# drivers.net
KiCad netlist of a schematic drawn in Altium Designer
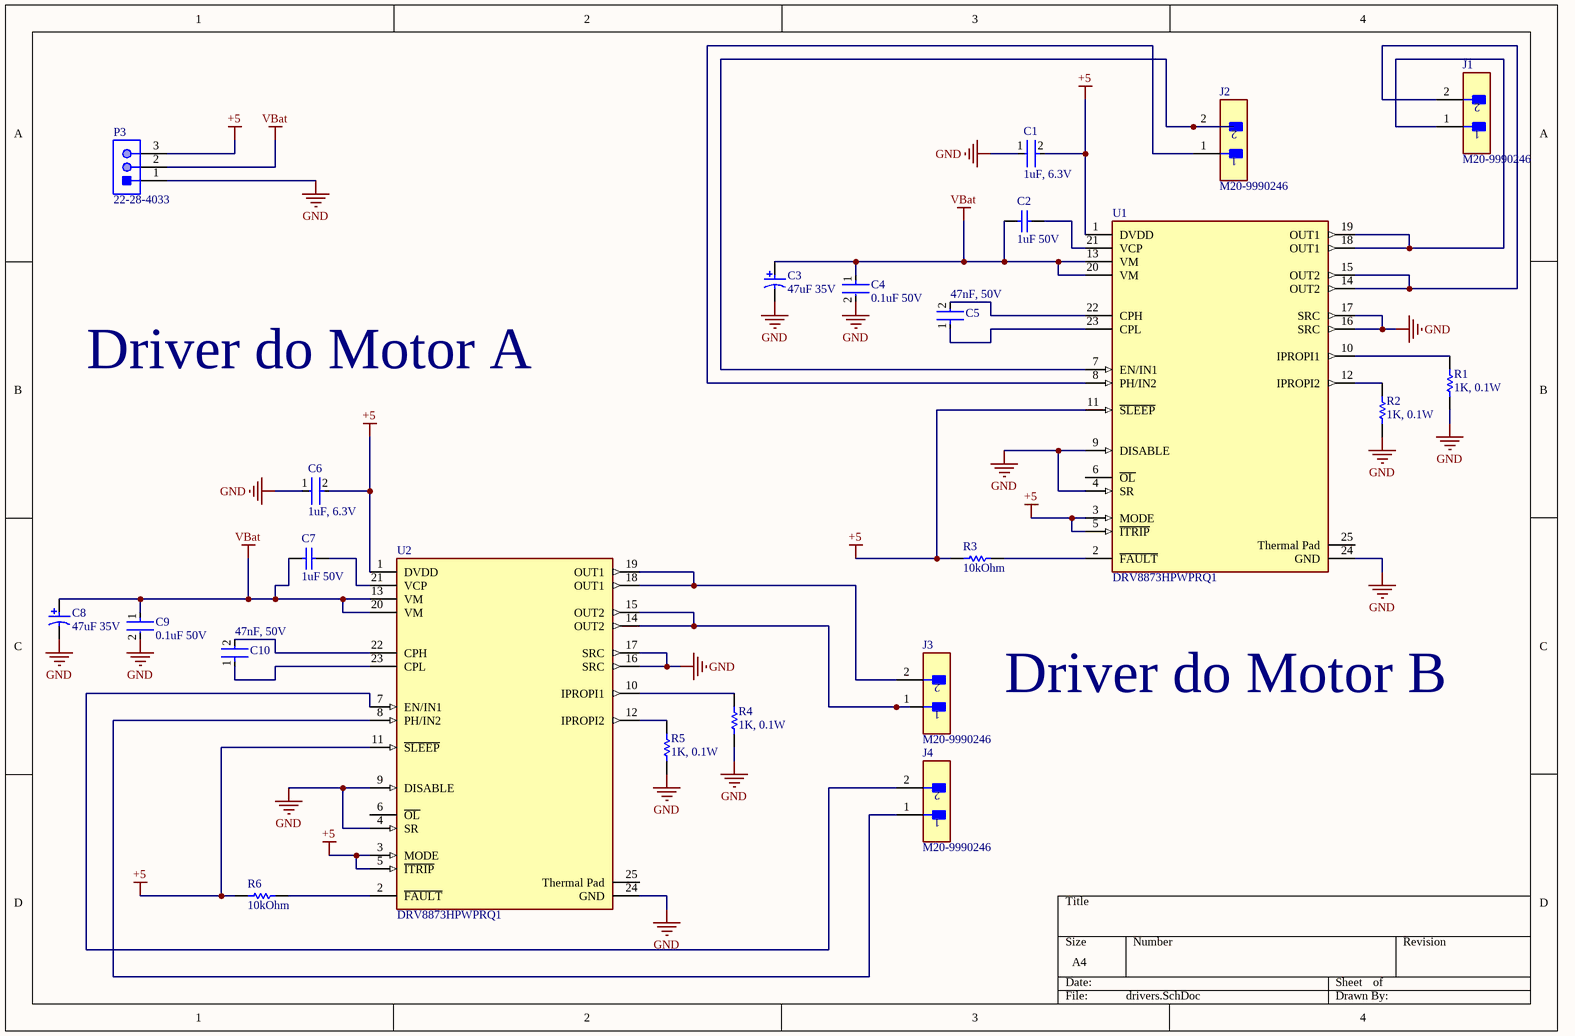
[diagram p0: drivers.SchDoc]

(export (version "E")
  (design (tool "Eeschema 10.0.6"))
  (components
    (comp (ref "C1")
      (value "1uF, 6.3V")
      (footprint "FP-GRM188-0_1-MFG")
      (description "CAP CER 1UF 6.3V X5R 0603")
      (fields (field (name "TOLERANCE") "10%") (field (name "VOLTAGE") "6.3V"))
      (libsource (lib "Altium Content Vault") (part "236180d848d6139a670b325ea6854c9"))
    )
    (comp (ref "C2")
      (value "1uF 50V")
      (footprint "CAPC1608X90X35ML10T25")
      (description "Chip Capacitor, 1 uF, +/- 10%, 50 V, -55 to 85 degC, 0603 (1608 Metric), RoHS, Tape and Reel")
      (fields (field (name "TOLERANCE") "±10%") (field (name "MANUFACTURER") "Taiyo Yuden"))
      (libsource (lib "Altium Content Vault") (part "CAP-NP-2"))
    )
    (comp (ref "C3")
      (value "47uF 35V")
      (footprint "PNSC-FP-V-D_V")
      (fields (field (name "MANUFACTURER") "Panasonic"))
      (libsource (lib "Altium Content Vault") (part "CAP-P-2"))
    )
    (comp (ref "C4")
      (value "0.1uF 50V")
      (footprint "FP-C0603-CJ-MFG")
      (description "CAP CER 0.1UF 50V X7R 0603")
      (fields (field (name "MANUFACTURER PART NUMBER") "C0603X104K5RACTU") (field (name "VOLTAGE") "50V"))
      (libsource (lib "Altium Content Vault") (part "11868f565c42a9108669ba33697ecf6"))
    )
    (comp (ref "C5")
      (value "47nF, 50V")
      (footprint "FP-C0603C-CF-MFG")
      (description "CAP CER 0.047UF 50V 10% X7R 0603")
      (fields (field (name "TOLERANCE") "0.1") (field (name "MANUFACTURER") "KEMET"))
      (libsource (lib "Altium Content Vault") (part "b4654b650e69147ec39a6b967a45e02"))
    )
    (comp (ref "C6")
      (value "1uF, 6.3V")
      (footprint "FP-GRM188-0_1-MFG")
      (description "CAP CER 1UF 6.3V X5R 0603")
      (fields (field (name "TOLERANCE") "10%") (field (name "VOLTAGE") "6.3V"))
      (libsource (lib "Altium Content Vault") (part "236180d848d6139a670b325ea6854c9"))
    )
    (comp (ref "C7")
      (value "1uF 50V")
      (footprint "CAPC1608X90X35ML10T25")
      (description "Chip Capacitor, 1 uF, +/- 10%, 50 V, -55 to 85 degC, 0603 (1608 Metric), RoHS, Tape and Reel")
      (fields (field (name "TOLERANCE") "±10%") (field (name "MANUFACTURER") "Taiyo Yuden"))
      (libsource (lib "Altium Content Vault") (part "CAP-NP-2"))
    )
    (comp (ref "C8")
      (value "47uF 35V")
      (footprint "PNSC-FP-V-D_V")
      (fields (field (name "MANUFACTURER") "Panasonic"))
      (libsource (lib "Altium Content Vault") (part "CAP-P-2"))
    )
    (comp (ref "C9")
      (value "0.1uF 50V")
      (footprint "FP-C0603-CJ-MFG")
      (description "CAP CER 0.1UF 50V X7R 0603")
      (fields (field (name "MANUFACTURER PART NUMBER") "C0603X104K5RACTU") (field (name "VOLTAGE") "50V"))
      (libsource (lib "Altium Content Vault") (part "11868f565c42a9108669ba33697ecf6"))
    )
    (comp (ref "C10")
      (value "47nF, 50V")
      (footprint "FP-C0603C-CF-MFG")
      (description "CAP CER 0.047UF 50V 10% X7R 0603")
      (fields (field (name "TOLERANCE") "0.1") (field (name "MANUFACTURER") "KEMET"))
      (libsource (lib "Altium Content Vault") (part "b4654b650e69147ec39a6b967a45e02"))
    )
    (comp (ref "J1")
      (value "M20-9990246")
      (footprint "FP-M20-9990246-MFG")
      (description "CONN HEADER VERT 2POS 2.54MM")
      (fields
        (field (name "OCTOPART") "https://octopart.com/m20-9990246-harwin-2590635")
        (field (name "MANUFACTURER") "Harwin")
      )
      (libsource (lib "Altium Content Vault") (part "3bc925449376181038e59eaffc5286c"))
    )
    (comp (ref "J2")
      (value "M20-9990246")
      (footprint "FP-M20-9990246-MFG")
      (description "CONN HEADER VERT 2POS 2.54MM")
      (fields
        (field (name "OCTOPART") "https://octopart.com/m20-9990246-harwin-2590635")
        (field (name "MANUFACTURER") "Harwin")
      )
      (libsource (lib "Altium Content Vault") (part "3bc925449376181038e59eaffc5286c"))
    )
    (comp (ref "J3")
      (value "M20-9990246")
      (footprint "FP-M20-9990246-MFG")
      (description "CONN HEADER VERT 2POS 2.54MM")
      (fields
        (field (name "OCTOPART") "https://octopart.com/m20-9990246-harwin-2590635")
        (field (name "MANUFACTURER") "Harwin")
      )
      (libsource (lib "Altium Content Vault") (part "3bc925449376181038e59eaffc5286c"))
    )
    (comp (ref "J4")
      (value "M20-9990246")
      (footprint "FP-M20-9990246-MFG")
      (description "CONN HEADER VERT 2POS 2.54MM")
      (fields
        (field (name "OCTOPART") "https://octopart.com/m20-9990246-harwin-2590635")
        (field (name "MANUFACTURER") "Harwin")
      )
      (libsource (lib "Altium Content Vault") (part "3bc925449376181038e59eaffc5286c"))
    )
    (comp (ref "P3")
      (value "22-28-4033")
      (footprint "MOLX-22-28-4033_V")
      (description "Male Header, Pitch 2.54 mm, 1 x 3 Position, Height 8.38 mm, Tail Length 3.18 mm, RoHS, Bulk")
      (fields (field (name "MANUFACTURER") "Molex"))
      (libsource (lib "Altium Content Vault") (part "CN-1P-M-R3"))
    )
    (comp (ref "R1")
      (value "1K, 0.1W")
      (footprint "RESC1608X55X30LL20T20")
      (fields (field (name "MANUFACTURER") "Panasonic") (field (name "PART NUMBER") "ERA3AEB102V"))
      (libsource (lib "Altium Content Vault") (part "RES"))
    )
    (comp (ref "R2")
      (value "1K, 0.1W")
      (footprint "RESC1608X55X30LL20T20")
      (fields (field (name "MANUFACTURER") "Panasonic") (field (name "PART NUMBER") "ERA3AEB102V"))
      (libsource (lib "Altium Content Vault") (part "RES"))
    )
    (comp (ref "R3")
      (value "10kOhm")
      (footprint "RESC1609X55X30LL15T15")
      (description "Chip Resistor, 10 KOhm, +/- 1%, 0.1 W, -55 to 155 degC, 0603 (1608 Metric), RoHS, Tape and Reel")
      (fields (field (name "TOLERANCE") "1%") (field (name "MANUFACTURER") "Panasonic"))
      (libsource (lib "Altium Content Vault") (part "RES-2"))
    )
    (comp (ref "R4")
      (value "1K, 0.1W")
      (footprint "RESC1608X55X30LL20T20")
      (fields (field (name "MANUFACTURER") "Panasonic") (field (name "PART NUMBER") "ERA3AEB102V"))
      (libsource (lib "Altium Content Vault") (part "RES"))
    )
    (comp (ref "R5")
      (value "1K, 0.1W")
      (footprint "RESC1608X55X30LL20T20")
      (fields (field (name "MANUFACTURER") "Panasonic") (field (name "PART NUMBER") "ERA3AEB102V"))
      (libsource (lib "Altium Content Vault") (part "RES"))
    )
    (comp (ref "R6")
      (value "10kOhm")
      (footprint "RESC1609X55X30LL15T15")
      (description "Chip Resistor, 10 KOhm, +/- 1%, 0.1 W, -55 to 155 degC, 0603 (1608 Metric), RoHS, Tape and Reel")
      (fields (field (name "TOLERANCE") "1%") (field (name "MANUFACTURER") "Panasonic"))
      (libsource (lib "Altium Content Vault") (part "RES-2"))
    )
    (comp (ref "U1")
      (value "DRV8873HPWPRQ1")
      (footprint "FP-PWP0024J-MFG")
      (description "IC MTRDRV UNIPLR 0-5.5V 24HTSSOP")
      (fields
        (field (name "OCTOPART") "https://octopart.com/drv8873hpwprq1-texas+instruments-94502234")
        (field (name "MANUFACTURER") "Texas Instruments")
      )
      (libsource (lib "Altium Content Vault") (part "d53c7614c064cbb015e0495e2bc09cf"))
    )
    (comp (ref "U2")
      (value "DRV8873HPWPRQ1")
      (footprint "FP-PWP0024J-MFG")
      (description "IC MTRDRV UNIPLR 0-5.5V 24HTSSOP")
      (fields
        (field (name "OCTOPART") "https://octopart.com/drv8873hpwprq1-texas+instruments-94502234")
        (field (name "MANUFACTURER") "Texas Instruments")
      )
      (libsource (lib "Altium Content Vault") (part "d53c7614c064cbb015e0495e2bc09cf"))
    )
  )
  (nets
    (net (code "1") (name "+5") (class "Default")
      (node (ref "C1") (pin "2") (pinfunction "2_2") (pintype "passive"))
      (node (ref "C6") (pin "2") (pinfunction "2_2") (pintype "passive"))
      (node (ref "P3") (pin "3") (pinfunction "3_3") (pintype "passive"))
      (node (ref "R3") (pin "1") (pinfunction "1_1") (pintype "passive"))
      (node (ref "R6") (pin "1") (pinfunction "1_1") (pintype "passive"))
      (node (ref "U1") (pin "1") (pinfunction "DVDD_1") (pintype "power_in"))
      (node (ref "U1") (pin "11") (pinfunction "~{SLEEP}_11") (pintype "input"))
      (node (ref "U1") (pin "3") (pinfunction "MODE_3") (pintype "input"))
      (node (ref "U1") (pin "5") (pinfunction "~{ITRIP}_5") (pintype "input"))
      (node (ref "U2") (pin "1") (pinfunction "DVDD_1") (pintype "power_in"))
      (node (ref "U2") (pin "11") (pinfunction "~{SLEEP}_11") (pintype "input"))
      (node (ref "U2") (pin "3") (pinfunction "MODE_3") (pintype "input"))
      (node (ref "U2") (pin "5") (pinfunction "~{ITRIP}_5") (pintype "input"))
    )
    (net (code "2") (name "GND") (class "Default")
      (node (ref "C1") (pin "1") (pinfunction "1_1") (pintype "passive"))
      (node (ref "C3") (pin "2") (pinfunction "2_2") (pintype "passive"))
      (node (ref "C4") (pin "2") (pinfunction "2_2") (pintype "passive"))
      (node (ref "C6") (pin "1") (pinfunction "1_1") (pintype "passive"))
      (node (ref "C8") (pin "2") (pinfunction "2_2") (pintype "passive"))
      (node (ref "C9") (pin "2") (pinfunction "2_2") (pintype "passive"))
      (node (ref "P3") (pin "1") (pinfunction "1_1") (pintype "passive"))
      (node (ref "R1") (pin "1") (pinfunction "1_1") (pintype "passive"))
      (node (ref "R2") (pin "1") (pinfunction "1_1") (pintype "passive"))
      (node (ref "R4") (pin "1") (pinfunction "1_1") (pintype "passive"))
      (node (ref "R5") (pin "1") (pinfunction "1_1") (pintype "passive"))
      (node (ref "U1") (pin "16") (pinfunction "SRC_16") (pintype "output"))
      (node (ref "U1") (pin "17") (pinfunction "SRC_17") (pintype "output"))
      (node (ref "U1") (pin "24") (pinfunction "GND_24") (pintype "power_in"))
      (node (ref "U1") (pin "4") (pinfunction "SR_4") (pintype "input"))
      (node (ref "U1") (pin "9") (pinfunction "DISABLE_9") (pintype "input"))
      (node (ref "U2") (pin "16") (pinfunction "SRC_16") (pintype "output"))
      (node (ref "U2") (pin "17") (pinfunction "SRC_17") (pintype "output"))
      (node (ref "U2") (pin "24") (pinfunction "GND_24") (pintype "power_in"))
      (node (ref "U2") (pin "4") (pinfunction "SR_4") (pintype "input"))
      (node (ref "U2") (pin "9") (pinfunction "DISABLE_9") (pintype "input"))
    )
    (net (code "3") (name "Net-(J1-Pad1)") (class "Default")
      (node (ref "J1") (pin "1") (pinfunction "1_1") (pintype "passive"))
      (node (ref "U1") (pin "18") (pinfunction "OUT1_18") (pintype "output"))
      (node (ref "U1") (pin "19") (pinfunction "OUT1_19") (pintype "output"))
    )
    (net (code "4") (name "Net-(J1-Pad2)") (class "Default")
      (node (ref "J1") (pin "2") (pinfunction "2_2") (pintype "passive"))
      (node (ref "U1") (pin "14") (pinfunction "OUT2_14") (pintype "output"))
      (node (ref "U1") (pin "15") (pinfunction "OUT2_15") (pintype "output"))
    )
    (net (code "5") (name "Net-(J3-Pad1)") (class "Default")
      (node (ref "J3") (pin "1") (pinfunction "1_1") (pintype "passive"))
      (node (ref "U2") (pin "14") (pinfunction "OUT2_14") (pintype "output"))
      (node (ref "U2") (pin "15") (pinfunction "OUT2_15") (pintype "output"))
    )
    (net (code "6") (name "Net-(J3-Pad2)") (class "Default")
      (node (ref "J3") (pin "2") (pinfunction "2_2") (pintype "passive"))
      (node (ref "U2") (pin "18") (pinfunction "OUT1_18") (pintype "output"))
      (node (ref "U2") (pin "19") (pinfunction "OUT1_19") (pintype "output"))
    )
    (net (code "7") (name "Net-(U1-CPH)") (class "Default")
      (node (ref "C5") (pin "2") (pinfunction "2_2") (pintype "passive"))
      (node (ref "U1") (pin "22") (pinfunction "CPH_22") (pintype "power_in"))
    )
    (net (code "8") (name "Net-(U1-CPL)") (class "Default")
      (node (ref "C5") (pin "1") (pinfunction "1_1") (pintype "passive"))
      (node (ref "U1") (pin "23") (pinfunction "CPL_23") (pintype "power_in"))
    )
    (net (code "9") (name "Net-(U1-EN{slash}IN1)") (class "Default")
      (node (ref "J2") (pin "2") (pinfunction "2_2") (pintype "passive"))
      (node (ref "U1") (pin "7") (pinfunction "EN/IN1_7") (pintype "input"))
    )
    (net (code "10") (name "Net-(U1-IPROPI1)") (class "Default")
      (node (ref "R1") (pin "2") (pinfunction "2_2") (pintype "passive"))
      (node (ref "U1") (pin "10") (pinfunction "IPROPI1_10") (pintype "output"))
    )
    (net (code "11") (name "Net-(U1-IPROPI2)") (class "Default")
      (node (ref "R2") (pin "2") (pinfunction "2_2") (pintype "passive"))
      (node (ref "U1") (pin "12") (pinfunction "IPROPI2_12") (pintype "output"))
    )
    (net (code "12") (name "Net-(U1-PH{slash}IN2)") (class "Default")
      (node (ref "J2") (pin "1") (pinfunction "1_1") (pintype "passive"))
      (node (ref "U1") (pin "8") (pinfunction "PH/IN2_8") (pintype "input"))
    )
    (net (code "13") (name "Net-(U1-VCP)") (class "Default")
      (node (ref "C2") (pin "2") (pinfunction "2_2") (pintype "passive"))
      (node (ref "U1") (pin "21") (pinfunction "VCP_21") (pintype "power_in"))
    )
    (net (code "14") (name "Net-(U1-~{FAULT})") (class "Default")
      (node (ref "R3") (pin "2") (pinfunction "2_2") (pintype "passive"))
      (node (ref "U1") (pin "2") (pinfunction "~{FAULT}_2") (pintype "open_collector"))
    )
    (net (code "15") (name "Net-(U2-CPH)") (class "Default")
      (node (ref "C10") (pin "2") (pinfunction "2_2") (pintype "passive"))
      (node (ref "U2") (pin "22") (pinfunction "CPH_22") (pintype "power_in"))
    )
    (net (code "16") (name "Net-(U2-CPL)") (class "Default")
      (node (ref "C10") (pin "1") (pinfunction "1_1") (pintype "passive"))
      (node (ref "U2") (pin "23") (pinfunction "CPL_23") (pintype "power_in"))
    )
    (net (code "17") (name "Net-(U2-EN{slash}IN1)") (class "Default")
      (node (ref "J4") (pin "2") (pinfunction "2_2") (pintype "passive"))
      (node (ref "U2") (pin "7") (pinfunction "EN/IN1_7") (pintype "input"))
    )
    (net (code "18") (name "Net-(U2-IPROPI1)") (class "Default")
      (node (ref "R4") (pin "2") (pinfunction "2_2") (pintype "passive"))
      (node (ref "U2") (pin "10") (pinfunction "IPROPI1_10") (pintype "output"))
    )
    (net (code "19") (name "Net-(U2-IPROPI2)") (class "Default")
      (node (ref "R5") (pin "2") (pinfunction "2_2") (pintype "passive"))
      (node (ref "U2") (pin "12") (pinfunction "IPROPI2_12") (pintype "output"))
    )
    (net (code "20") (name "Net-(U2-PH{slash}IN2)") (class "Default")
      (node (ref "J4") (pin "1") (pinfunction "1_1") (pintype "passive"))
      (node (ref "U2") (pin "8") (pinfunction "PH/IN2_8") (pintype "input"))
    )
    (net (code "21") (name "Net-(U2-VCP)") (class "Default")
      (node (ref "C7") (pin "2") (pinfunction "2_2") (pintype "passive"))
      (node (ref "U2") (pin "21") (pinfunction "VCP_21") (pintype "power_in"))
    )
    (net (code "22") (name "Net-(U2-~{FAULT})") (class "Default")
      (node (ref "R6") (pin "2") (pinfunction "2_2") (pintype "passive"))
      (node (ref "U2") (pin "2") (pinfunction "~{FAULT}_2") (pintype "open_collector"))
    )
    (net (code "23") (name "VBat") (class "Default")
      (node (ref "C2") (pin "1") (pinfunction "1_1") (pintype "passive"))
      (node (ref "C3") (pin "1") (pinfunction "1_1") (pintype "passive"))
      (node (ref "C4") (pin "1") (pinfunction "1_1") (pintype "passive"))
      (node (ref "C7") (pin "1") (pinfunction "1_1") (pintype "passive"))
      (node (ref "C8") (pin "1") (pinfunction "1_1") (pintype "passive"))
      (node (ref "C9") (pin "1") (pinfunction "1_1") (pintype "passive"))
      (node (ref "P3") (pin "2") (pinfunction "2_2") (pintype "passive"))
      (node (ref "U1") (pin "13") (pinfunction "VM_13") (pintype "power_in"))
      (node (ref "U1") (pin "20") (pinfunction "VM_20") (pintype "power_in"))
      (node (ref "U2") (pin "13") (pinfunction "VM_13") (pintype "power_in"))
      (node (ref "U2") (pin "20") (pinfunction "VM_20") (pintype "power_in"))
    )
    (net (code "24") (name "unconnected-(U1-Thermal_Pad-Pad25)") (class "Default")
      (node (ref "U1") (pin "25") (pinfunction "Thermal_Pad_25") (pintype "power_in"))
    )
    (net (code "25") (name "unconnected-(U1-~{OL}-Pad6)") (class "Default")
      (node (ref "U1") (pin "6") (pinfunction "~{OL}_6") (pintype "open_collector"))
    )
    (net (code "26") (name "unconnected-(U2-Thermal_Pad-Pad25)") (class "Default")
      (node (ref "U2") (pin "25") (pinfunction "Thermal_Pad_25") (pintype "power_in"))
    )
    (net (code "27") (name "unconnected-(U2-~{OL}-Pad6)") (class "Default")
      (node (ref "U2") (pin "6") (pinfunction "~{OL}_6") (pintype "open_collector"))
    )
  )
)
